# SFP.net
KiCad netlist of a schematic drawn in Altium Designer
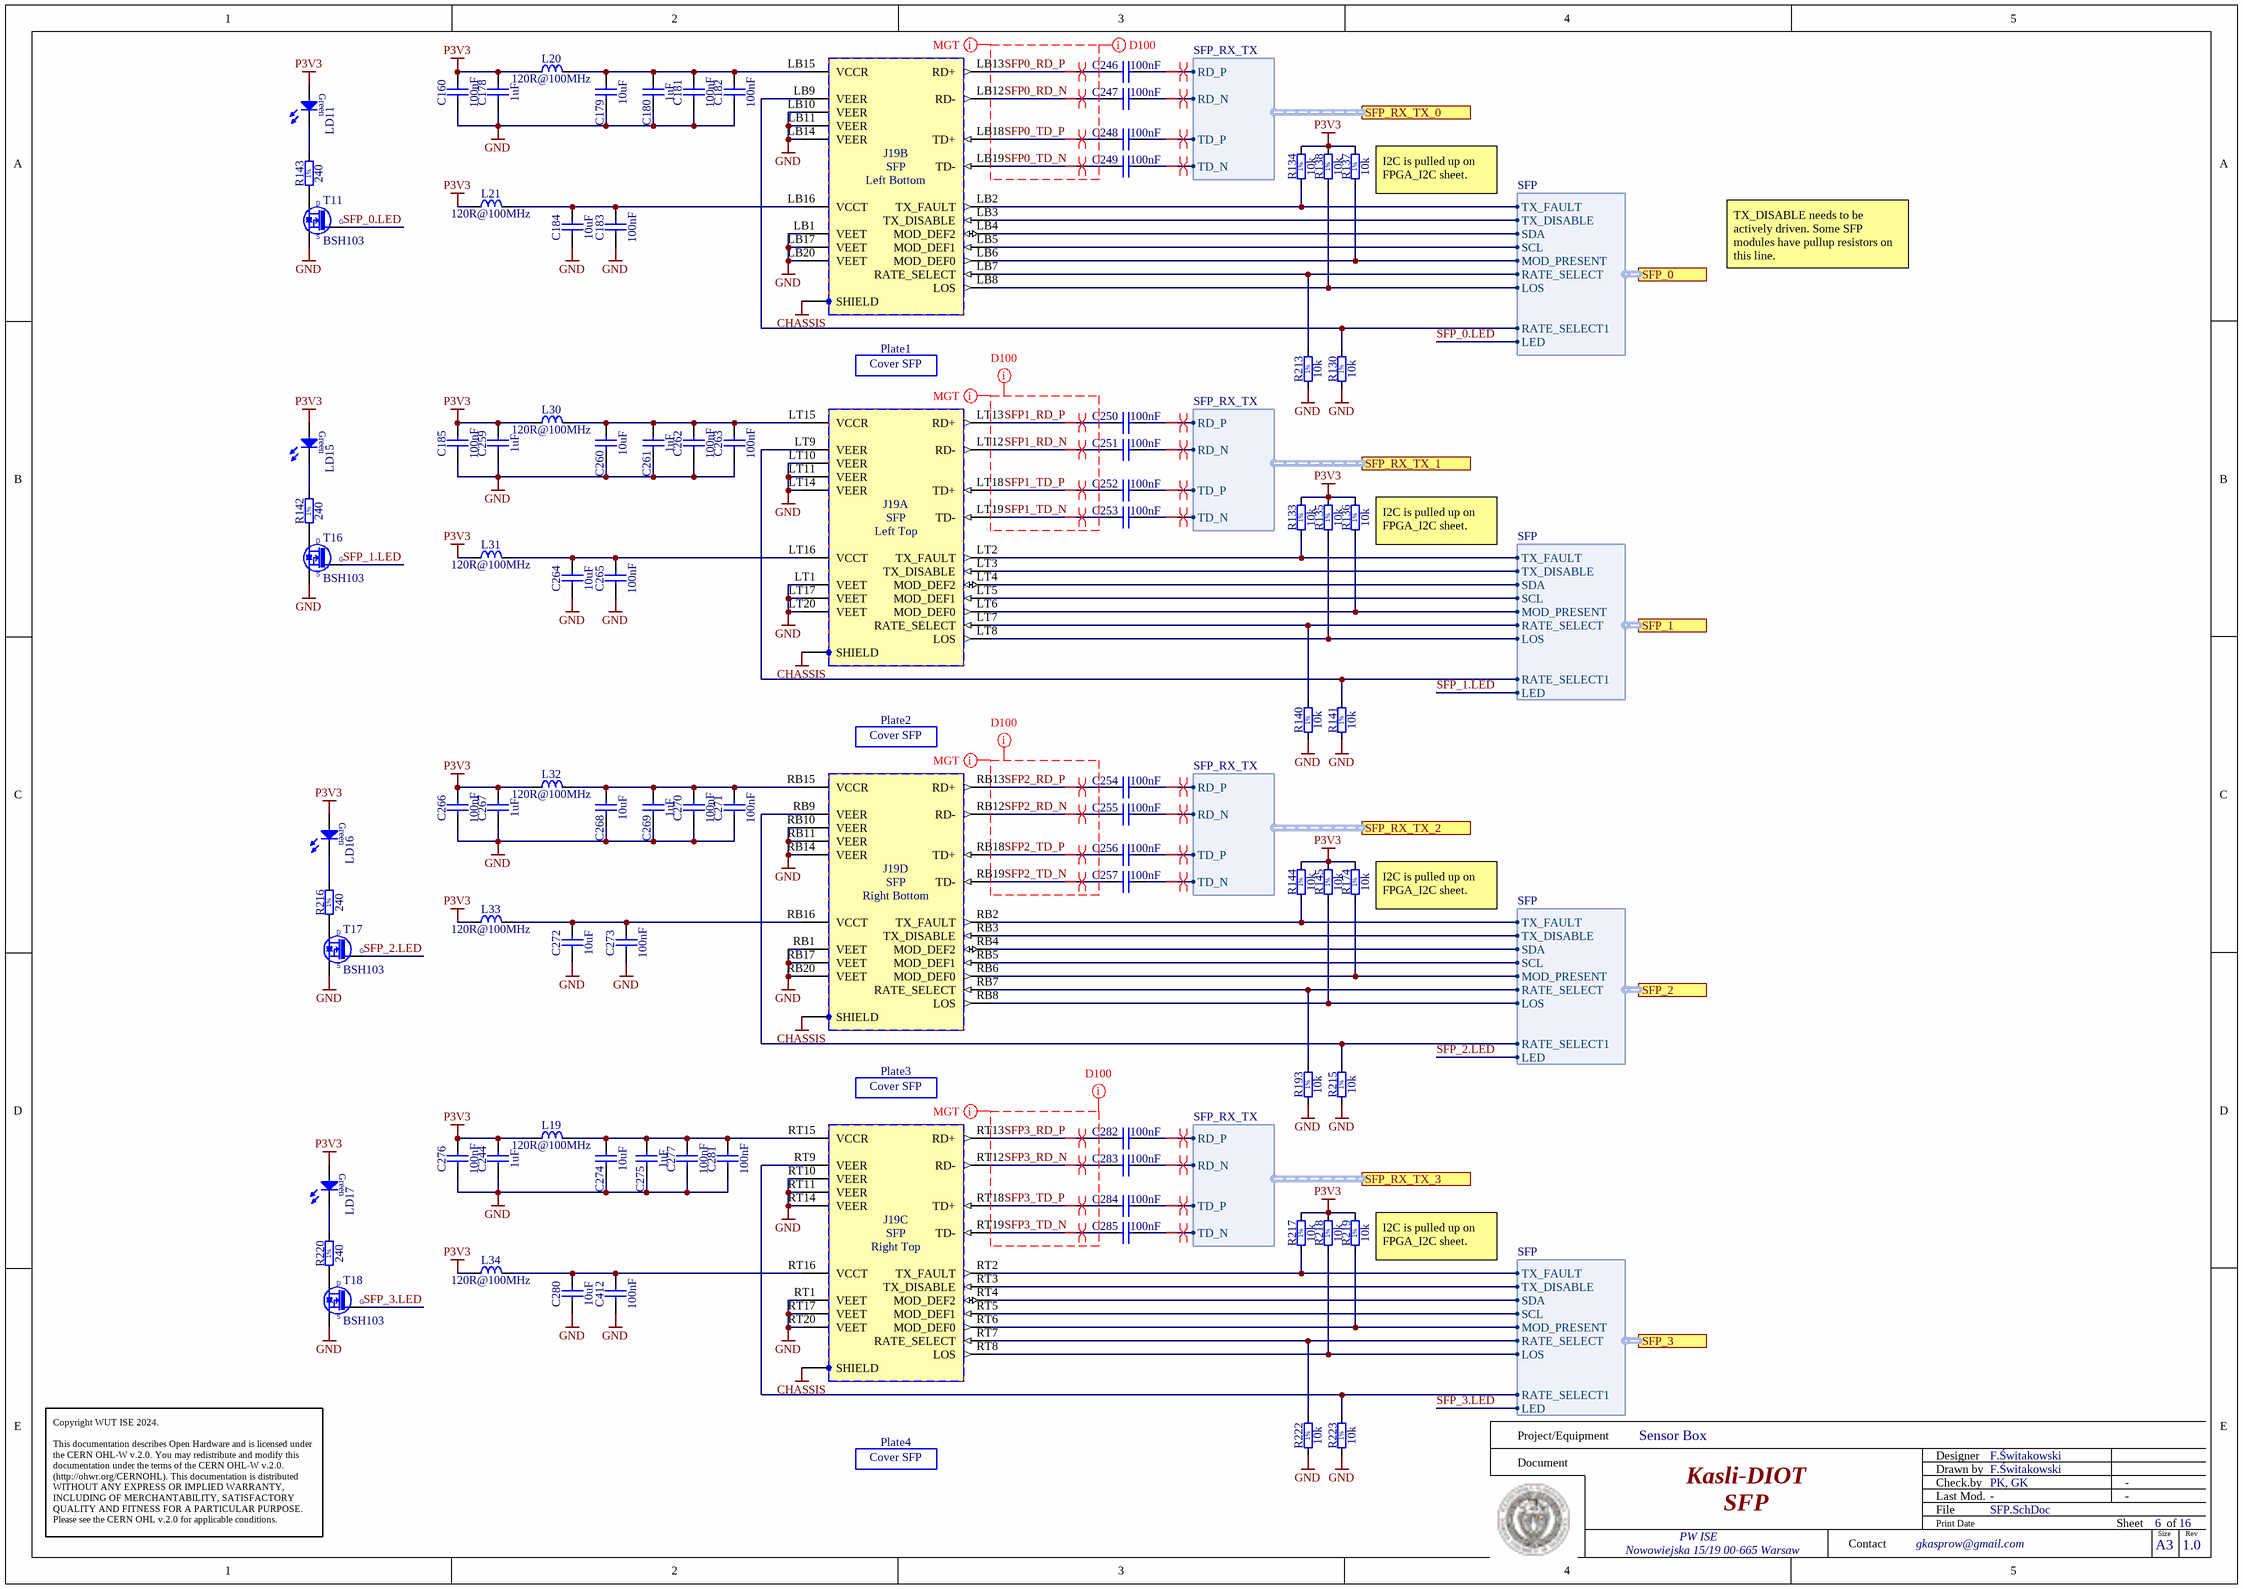
[diagram p0: SFP.SchDoc]

(export (version "E")
  (design (tool "Eeschema 10.0.6"))
  (components
    (comp (ref "C160")
      (value "100nF")
      (footprint "CAPC1005X55N")
      (description "Non-polarised capacitor")
      (fields (field (name "PART NUMBER") "CC0402_100NF_16V_10%_X7R") (field (name "VOLTAGE") "16V"))
      (libsource (lib "Capacitors") (part "Capacitor - non polarized"))
    )
    (comp (ref "C178")
      (value "1uF")
      (footprint "CAPC1005X55N")
      (description "Non-polarised capacitor")
      (fields (field (name "PART NUMBER") "CC0402_1UF_16V_10%_X5R") (field (name "VOLTAGE") "16V"))
      (libsource (lib "Capacitors") (part "Capacitor - non polarized"))
    )
    (comp (ref "C179")
      (value "10uF")
      (footprint "CAPC2012X95N")
      (description "Non-polarised capacitor")
      (fields (field (name "PART NUMBER") "CC0805_10UF_25V_10%_X5R") (field (name "VOLTAGE") "25V"))
      (libsource (lib "Capacitors") (part "Capacitor - non polarized"))
    )
    (comp (ref "C180")
      (value "1uF")
      (footprint "CAPC1005X55N")
      (description "Non-polarised capacitor")
      (fields (field (name "PART NUMBER") "CC0402_1UF_16V_10%_X5R") (field (name "VOLTAGE") "16V"))
      (libsource (lib "Capacitors") (part "Capacitor - non polarized"))
    )
    (comp (ref "C181")
      (value "100nF")
      (footprint "CAPC1005X55N")
      (description "Non-polarised capacitor")
      (fields (field (name "PART NUMBER") "CC0402_100NF_16V_10%_X7R") (field (name "VOLTAGE") "16V"))
      (libsource (lib "Capacitors") (part "Capacitor - non polarized"))
    )
    (comp (ref "C182")
      (value "100nF")
      (footprint "CAPC1005X55N")
      (description "Non-polarised capacitor")
      (fields (field (name "PART NUMBER") "CC0402_100NF_16V_10%_X7R") (field (name "VOLTAGE") "16V"))
      (libsource (lib "Capacitors") (part "Capacitor - non polarized"))
    )
    (comp (ref "C183")
      (value "100nF")
      (footprint "CAPC1005X55N")
      (description "Non-polarised capacitor")
      (fields (field (name "PART NUMBER") "CC0402_100NF_16V_10%_X7R") (field (name "VOLTAGE") "16V"))
      (libsource (lib "Capacitors") (part "Capacitor - non polarized"))
    )
    (comp (ref "C184")
      (value "10uF")
      (footprint "CAPC2012X95N")
      (description "Non-polarised capacitor")
      (fields (field (name "PART NUMBER") "CC0805_10UF_25V_10%_X5R") (field (name "VOLTAGE") "25V"))
      (libsource (lib "Capacitors") (part "Capacitor - non polarized"))
    )
    (comp (ref "C185")
      (value "100nF")
      (footprint "CAPC1005X55N")
      (description "Non-polarised capacitor")
      (fields (field (name "PART NUMBER") "CC0402_100NF_16V_10%_X7R") (field (name "VOLTAGE") "16V"))
      (libsource (lib "Capacitors") (part "Capacitor - non polarized"))
    )
    (comp (ref "C244")
      (value "1uF")
      (footprint "CAPC1005X55N")
      (description "Non-polarised capacitor")
      (fields (field (name "PART NUMBER") "CC0402_1UF_16V_10%_X5R") (field (name "VOLTAGE") "16V"))
      (libsource (lib "Capacitors") (part "Capacitor - non polarized"))
    )
    (comp (ref "C246")
      (value "100nF")
      (footprint "CAPC0603X33N")
      (description "Non-polarised capacitor")
      (fields (field (name "PART NUMBER") "CC0201_100NF_6.3V_10%_X5R") (field (name "VOLTAGE") "6.3V"))
      (libsource (lib "Capacitors") (part "Capacitor - non polarized"))
    )
    (comp (ref "C247")
      (value "100nF")
      (footprint "CAPC0603X33N")
      (description "Non-polarised capacitor")
      (fields (field (name "PART NUMBER") "CC0201_100NF_6.3V_10%_X5R") (field (name "VOLTAGE") "6.3V"))
      (libsource (lib "Capacitors") (part "Capacitor - non polarized"))
    )
    (comp (ref "C248")
      (value "100nF")
      (footprint "CAPC0603X33N")
      (description "Non-polarised capacitor")
      (fields (field (name "PART NUMBER") "CC0201_100NF_6.3V_10%_X5R") (field (name "VOLTAGE") "6.3V"))
      (libsource (lib "Capacitors") (part "Capacitor - non polarized"))
    )
    (comp (ref "C249")
      (value "100nF")
      (footprint "CAPC0603X33N")
      (description "Non-polarised capacitor")
      (fields (field (name "PART NUMBER") "CC0201_100NF_6.3V_10%_X5R") (field (name "VOLTAGE") "6.3V"))
      (libsource (lib "Capacitors") (part "Capacitor - non polarized"))
    )
    (comp (ref "C250")
      (value "100nF")
      (footprint "CAPC0603X33N")
      (description "Non-polarised capacitor")
      (fields (field (name "PART NUMBER") "CC0201_100NF_6.3V_10%_X5R") (field (name "VOLTAGE") "6.3V"))
      (libsource (lib "Capacitors") (part "Capacitor - non polarized"))
    )
    (comp (ref "C251")
      (value "100nF")
      (footprint "CAPC0603X33N")
      (description "Non-polarised capacitor")
      (fields (field (name "PART NUMBER") "CC0201_100NF_6.3V_10%_X5R") (field (name "VOLTAGE") "6.3V"))
      (libsource (lib "Capacitors") (part "Capacitor - non polarized"))
    )
    (comp (ref "C252")
      (value "100nF")
      (footprint "CAPC0603X33N")
      (description "Non-polarised capacitor")
      (fields (field (name "PART NUMBER") "CC0201_100NF_6.3V_10%_X5R") (field (name "VOLTAGE") "6.3V"))
      (libsource (lib "Capacitors") (part "Capacitor - non polarized"))
    )
    (comp (ref "C253")
      (value "100nF")
      (footprint "CAPC0603X33N")
      (description "Non-polarised capacitor")
      (fields (field (name "PART NUMBER") "CC0201_100NF_6.3V_10%_X5R") (field (name "VOLTAGE") "6.3V"))
      (libsource (lib "Capacitors") (part "Capacitor - non polarized"))
    )
    (comp (ref "C254")
      (value "100nF")
      (footprint "CAPC0603X33N")
      (description "Non-polarised capacitor")
      (fields (field (name "PART NUMBER") "CC0201_100NF_6.3V_10%_X5R") (field (name "VOLTAGE") "6.3V"))
      (libsource (lib "Capacitors") (part "Capacitor - non polarized"))
    )
    (comp (ref "C255")
      (value "100nF")
      (footprint "CAPC0603X33N")
      (description "Non-polarised capacitor")
      (fields (field (name "PART NUMBER") "CC0201_100NF_6.3V_10%_X5R") (field (name "VOLTAGE") "6.3V"))
      (libsource (lib "Capacitors") (part "Capacitor - non polarized"))
    )
    (comp (ref "C256")
      (value "100nF")
      (footprint "CAPC0603X33N")
      (description "Non-polarised capacitor")
      (fields (field (name "PART NUMBER") "CC0201_100NF_6.3V_10%_X5R") (field (name "VOLTAGE") "6.3V"))
      (libsource (lib "Capacitors") (part "Capacitor - non polarized"))
    )
    (comp (ref "C257")
      (value "100nF")
      (footprint "CAPC0603X33N")
      (description "Non-polarised capacitor")
      (fields (field (name "PART NUMBER") "CC0201_100NF_6.3V_10%_X5R") (field (name "VOLTAGE") "6.3V"))
      (libsource (lib "Capacitors") (part "Capacitor - non polarized"))
    )
    (comp (ref "C259")
      (value "1uF")
      (footprint "CAPC1005X55N")
      (description "Non-polarised capacitor")
      (fields (field (name "PART NUMBER") "CC0402_1UF_16V_10%_X5R") (field (name "VOLTAGE") "16V"))
      (libsource (lib "Capacitors") (part "Capacitor - non polarized"))
    )
    (comp (ref "C260")
      (value "10uF")
      (footprint "CAPC2012X95N")
      (description "Non-polarised capacitor")
      (fields (field (name "PART NUMBER") "CC0805_10UF_25V_10%_X5R") (field (name "VOLTAGE") "25V"))
      (libsource (lib "Capacitors") (part "Capacitor - non polarized"))
    )
    (comp (ref "C261")
      (value "1uF")
      (footprint "CAPC1005X55N")
      (description "Non-polarised capacitor")
      (fields (field (name "PART NUMBER") "CC0402_1UF_16V_10%_X5R") (field (name "VOLTAGE") "16V"))
      (libsource (lib "Capacitors") (part "Capacitor - non polarized"))
    )
    (comp (ref "C262")
      (value "100nF")
      (footprint "CAPC1005X55N")
      (description "Non-polarised capacitor")
      (fields (field (name "PART NUMBER") "CC0402_100NF_16V_10%_X7R") (field (name "VOLTAGE") "16V"))
      (libsource (lib "Capacitors") (part "Capacitor - non polarized"))
    )
    (comp (ref "C263")
      (value "100nF")
      (footprint "CAPC1005X55N")
      (description "Non-polarised capacitor")
      (fields (field (name "PART NUMBER") "CC0402_100NF_16V_10%_X7R") (field (name "VOLTAGE") "16V"))
      (libsource (lib "Capacitors") (part "Capacitor - non polarized"))
    )
    (comp (ref "C264")
      (value "10uF")
      (footprint "CAPC2012X95N")
      (description "Non-polarised capacitor")
      (fields (field (name "PART NUMBER") "CC0805_10UF_25V_10%_X5R") (field (name "VOLTAGE") "25V"))
      (libsource (lib "Capacitors") (part "Capacitor - non polarized"))
    )
    (comp (ref "C265")
      (value "100nF")
      (footprint "CAPC1005X55N")
      (description "Non-polarised capacitor")
      (fields (field (name "PART NUMBER") "CC0402_100NF_16V_10%_X7R") (field (name "VOLTAGE") "16V"))
      (libsource (lib "Capacitors") (part "Capacitor - non polarized"))
    )
    (comp (ref "C266")
      (value "100nF")
      (footprint "CAPC1005X55N")
      (description "Non-polarised capacitor")
      (fields (field (name "PART NUMBER") "CC0402_100NF_16V_10%_X7R") (field (name "VOLTAGE") "16V"))
      (libsource (lib "Capacitors") (part "Capacitor - non polarized"))
    )
    (comp (ref "C267")
      (value "1uF")
      (footprint "CAPC1005X55N")
      (description "Non-polarised capacitor")
      (fields (field (name "PART NUMBER") "CC0402_1UF_16V_10%_X5R") (field (name "VOLTAGE") "16V"))
      (libsource (lib "Capacitors") (part "Capacitor - non polarized"))
    )
    (comp (ref "C268")
      (value "10uF")
      (footprint "CAPC2012X95N")
      (description "Non-polarised capacitor")
      (fields (field (name "PART NUMBER") "CC0805_10UF_25V_10%_X5R") (field (name "VOLTAGE") "25V"))
      (libsource (lib "Capacitors") (part "Capacitor - non polarized"))
    )
    (comp (ref "C269")
      (value "1uF")
      (footprint "CAPC1005X55N")
      (description "Non-polarised capacitor")
      (fields (field (name "PART NUMBER") "CC0402_1UF_16V_10%_X5R") (field (name "VOLTAGE") "16V"))
      (libsource (lib "Capacitors") (part "Capacitor - non polarized"))
    )
    (comp (ref "C270")
      (value "100nF")
      (footprint "CAPC1005X55N")
      (description "Non-polarised capacitor")
      (fields (field (name "PART NUMBER") "CC0402_100NF_16V_10%_X7R") (field (name "VOLTAGE") "16V"))
      (libsource (lib "Capacitors") (part "Capacitor - non polarized"))
    )
    (comp (ref "C271")
      (value "100nF")
      (footprint "CAPC1005X55N")
      (description "Non-polarised capacitor")
      (fields (field (name "PART NUMBER") "CC0402_100NF_16V_10%_X7R") (field (name "VOLTAGE") "16V"))
      (libsource (lib "Capacitors") (part "Capacitor - non polarized"))
    )
    (comp (ref "C272")
      (value "10uF")
      (footprint "CAPC2012X95N")
      (description "Non-polarised capacitor")
      (fields (field (name "PART NUMBER") "CC0805_10UF_25V_10%_X5R") (field (name "VOLTAGE") "25V"))
      (libsource (lib "Capacitors") (part "Capacitor - non polarized"))
    )
    (comp (ref "C273")
      (value "100nF")
      (footprint "CAPC1005X55N")
      (description "Non-polarised capacitor")
      (fields (field (name "PART NUMBER") "CC0402_100NF_16V_10%_X7R") (field (name "VOLTAGE") "16V"))
      (libsource (lib "Capacitors") (part "Capacitor - non polarized"))
    )
    (comp (ref "C274")
      (value "10uF")
      (footprint "CAPC2012X95N")
      (description "Non-polarised capacitor")
      (fields (field (name "PART NUMBER") "CC0805_10UF_25V_10%_X5R") (field (name "VOLTAGE") "25V"))
      (libsource (lib "Capacitors") (part "Capacitor - non polarized"))
    )
    (comp (ref "C275")
      (value "1uF")
      (footprint "CAPC1005X55N")
      (description "Non-polarised capacitor")
      (fields (field (name "PART NUMBER") "CC0402_1UF_16V_10%_X5R") (field (name "VOLTAGE") "16V"))
      (libsource (lib "Capacitors") (part "Capacitor - non polarized"))
    )
    (comp (ref "C276")
      (value "100nF")
      (footprint "CAPC1005X55N")
      (description "Non-polarised capacitor")
      (fields (field (name "PART NUMBER") "CC0402_100NF_16V_10%_X7R") (field (name "VOLTAGE") "16V"))
      (libsource (lib "Capacitors") (part "Capacitor - non polarized"))
    )
    (comp (ref "C277")
      (value "100nF")
      (footprint "CAPC1005X55N")
      (description "Non-polarised capacitor")
      (fields (field (name "PART NUMBER") "CC0402_100NF_16V_10%_X7R") (field (name "VOLTAGE") "16V"))
      (libsource (lib "Capacitors") (part "Capacitor - non polarized"))
    )
    (comp (ref "C280")
      (value "10uF")
      (footprint "CAPC2012X95N")
      (description "Non-polarised capacitor")
      (fields (field (name "PART NUMBER") "CC0805_10UF_25V_10%_X5R") (field (name "VOLTAGE") "25V"))
      (libsource (lib "Capacitors") (part "Capacitor - non polarized"))
    )
    (comp (ref "C281")
      (value "100nF")
      (footprint "CAPC1005X55N")
      (description "Non-polarised capacitor")
      (fields (field (name "PART NUMBER") "CC0402_100NF_16V_10%_X7R") (field (name "VOLTAGE") "16V"))
      (libsource (lib "Capacitors") (part "Capacitor - non polarized"))
    )
    (comp (ref "C282")
      (value "100nF")
      (footprint "CAPC0603X33N")
      (description "Non-polarised capacitor")
      (fields (field (name "PART NUMBER") "CC0201_100NF_6.3V_10%_X5R") (field (name "VOLTAGE") "6.3V"))
      (libsource (lib "Capacitors") (part "Capacitor - non polarized"))
    )
    (comp (ref "C283")
      (value "100nF")
      (footprint "CAPC0603X33N")
      (description "Non-polarised capacitor")
      (fields (field (name "PART NUMBER") "CC0201_100NF_6.3V_10%_X5R") (field (name "VOLTAGE") "6.3V"))
      (libsource (lib "Capacitors") (part "Capacitor - non polarized"))
    )
    (comp (ref "C284")
      (value "100nF")
      (footprint "CAPC0603X33N")
      (description "Non-polarised capacitor")
      (fields (field (name "PART NUMBER") "CC0201_100NF_6.3V_10%_X5R") (field (name "VOLTAGE") "6.3V"))
      (libsource (lib "Capacitors") (part "Capacitor - non polarized"))
    )
    (comp (ref "C285")
      (value "100nF")
      (footprint "CAPC0603X33N")
      (description "Non-polarised capacitor")
      (fields (field (name "PART NUMBER") "CC0201_100NF_6.3V_10%_X5R") (field (name "VOLTAGE") "6.3V"))
      (libsource (lib "Capacitors") (part "Capacitor - non polarized"))
    )
    (comp (ref "C412")
      (value "100nF")
      (footprint "CAPC1005X55N")
      (description "Non-polarised capacitor")
      (fields (field (name "PART NUMBER") "CC0402_100NF_16V_10%_X7R") (field (name "VOLTAGE") "16V"))
      (libsource (lib "Capacitors") (part "Capacitor - non polarized"))
    )
    (comp (ref "J19")
      (value "SFP")
      (footprint "AMPHENOL_UE78B212700321")
      (description "20 Position SFP  Connector (Small Form-factor Pluggable)")
      (fields (field (name "PART NUMBER") "AMPHENOL_UE78B212700321") (field (name "MANUFACTURER") "AMPHENOL"))
      (libsource (lib "Connectors") (part "SFP 2x2 +Cage"))
    )
    (comp (ref "L19")
      (value "120R@100MHz")
      (footprint "INDC1608X65N")
      (description "Inductor")
      (fields (field (name "PART NUMBER") "IND0603_MURATA_BLM18SG121TN1D") (field (name "POWER") "3A"))
      (libsource (lib "Inductors & Transformers") (part "Inductor"))
    )
    (comp (ref "L20")
      (value "120R@100MHz")
      (footprint "INDC1608X65N")
      (description "Inductor")
      (fields (field (name "PART NUMBER") "IND0603_MURATA_BLM18SG121TN1D") (field (name "POWER") "3A"))
      (libsource (lib "Inductors & Transformers") (part "Inductor"))
    )
    (comp (ref "L21")
      (value "120R@100MHz")
      (footprint "INDC1608X65N")
      (description "Inductor")
      (fields (field (name "PART NUMBER") "IND0603_MURATA_BLM18SG121TN1D") (field (name "POWER") "3A"))
      (libsource (lib "Inductors & Transformers") (part "Inductor"))
    )
    (comp (ref "L30")
      (value "120R@100MHz")
      (footprint "INDC1608X65N")
      (description "Inductor")
      (fields (field (name "PART NUMBER") "IND0603_MURATA_BLM18SG121TN1D") (field (name "POWER") "3A"))
      (libsource (lib "Inductors & Transformers") (part "Inductor"))
    )
    (comp (ref "L31")
      (value "120R@100MHz")
      (footprint "INDC1608X65N")
      (description "Inductor")
      (fields (field (name "PART NUMBER") "IND0603_MURATA_BLM18SG121TN1D") (field (name "POWER") "3A"))
      (libsource (lib "Inductors & Transformers") (part "Inductor"))
    )
    (comp (ref "L32")
      (value "120R@100MHz")
      (footprint "INDC1608X65N")
      (description "Inductor")
      (fields (field (name "PART NUMBER") "IND0603_MURATA_BLM18SG121TN1D") (field (name "POWER") "3A"))
      (libsource (lib "Inductors & Transformers") (part "Inductor"))
    )
    (comp (ref "L33")
      (value "120R@100MHz")
      (footprint "INDC1608X65N")
      (description "Inductor")
      (fields (field (name "PART NUMBER") "IND0603_MURATA_BLM18SG121TN1D") (field (name "POWER") "3A"))
      (libsource (lib "Inductors & Transformers") (part "Inductor"))
    )
    (comp (ref "L34")
      (value "120R@100MHz")
      (footprint "INDC1608X65N")
      (description "Inductor")
      (fields (field (name "PART NUMBER") "IND0603_MURATA_BLM18SG121TN1D") (field (name "POWER") "3A"))
      (libsource (lib "Inductors & Transformers") (part "Inductor"))
    )
    (comp (ref "LD11")
      (value "Green")
      (footprint "LED_AVAGO_HSME-C120")
      (description "LED Green 1C 2A")
      (fields
        (field (name "PART NUMBER") "LED_AVAGO_HSME-C120")
        (field (name "MANUFACTURER") "AVAGO TECHNOLOGIES")
      )
      (libsource (lib "ICs And Semiconductors") (part "LED Green 1C 2A"))
    )
    (comp (ref "LD15")
      (value "Green")
      (footprint "LED_AVAGO_HSME-C120")
      (description "LED Green 1C 2A")
      (fields
        (field (name "PART NUMBER") "LED_AVAGO_HSME-C120")
        (field (name "MANUFACTURER") "AVAGO TECHNOLOGIES")
      )
      (libsource (lib "ICs And Semiconductors") (part "LED Green 1C 2A"))
    )
    (comp (ref "LD16")
      (value "Green")
      (footprint "LED_AVAGO_HSME-C120")
      (description "LED Green 1C 2A")
      (fields
        (field (name "PART NUMBER") "LED_AVAGO_HSME-C120")
        (field (name "MANUFACTURER") "AVAGO TECHNOLOGIES")
      )
      (libsource (lib "ICs And Semiconductors") (part "LED Green 1C 2A"))
    )
    (comp (ref "LD17")
      (value "Green")
      (footprint "LED_AVAGO_HSME-C120")
      (description "LED Green 1C 2A")
      (fields
        (field (name "PART NUMBER") "LED_AVAGO_HSME-C120")
        (field (name "MANUFACTURER") "AVAGO TECHNOLOGIES")
      )
      (libsource (lib "ICs And Semiconductors") (part "LED Green 1C 2A"))
    )
    (comp (ref "Plate1")
      (value "Cover SFP")
      (footprint "AMPHENOL_U77A11108000P")
      (description "Plastic Dust Cover SFP Cage")
      (fields (field (name "PART NUMBER") "AMPHENOL_U77A11108000P") (field (name "MANUFACTURER") "AMPHENOL"))
      (libsource (lib "Eletro-mechanical") (part "SFP Cover No Pin"))
    )
    (comp (ref "Plate2")
      (value "Cover SFP")
      (footprint "AMPHENOL_U77A11108000P")
      (description "Plastic Dust Cover SFP Cage")
      (fields
        (field (name "MANUFACTURER") "AMPHENOL")
        (field (name "MANUFACTURER PART NUMBER") "U77A11108000P")
      )
      (libsource (lib "Eletro-mechanical") (part "SFP Cover No Pin"))
    )
    (comp (ref "Plate3")
      (value "Cover SFP")
      (footprint "AMPHENOL_U77A11108000P")
      (description "Plastic Dust Cover SFP Cage")
      (fields
        (field (name "MANUFACTURER") "AMPHENOL")
        (field (name "MANUFACTURER PART NUMBER") "U77A11108000P")
      )
      (libsource (lib "Eletro-mechanical") (part "SFP Cover No Pin"))
    )
    (comp (ref "Plate4")
      (value "Cover SFP")
      (footprint "AMPHENOL_U77A11108000P")
      (description "Plastic Dust Cover SFP Cage")
      (fields
        (field (name "MANUFACTURER") "AMPHENOL")
        (field (name "MANUFACTURER PART NUMBER") "U77A11108000P")
      )
      (libsource (lib "Eletro-mechanical") (part "SFP Cover No Pin"))
    )
    (comp (ref "R130")
      (value "10k")
      (footprint "RESC1005X40N")
      (description "Resistor - 1%")
      (fields (field (name "PART NUMBER") "R0402_10K_1%_0.0625W_100PPM") (field (name "POWER") "0.0625W"))
      (libsource (lib "Resistors") (part "Resistor - 1%"))
    )
    (comp (ref "R133")
      (value "10k")
      (footprint "RESC1005X40N")
      (description "Resistor - 1%")
      (fields (field (name "PART NUMBER") "R0402_10K_1%_0.0625W_100PPM") (field (name "POWER") "0.0625W"))
      (libsource (lib "Resistors") (part "Resistor - 1%"))
    )
    (comp (ref "R134")
      (value "10k")
      (footprint "RESC1005X40N")
      (description "Resistor - 1%")
      (fields (field (name "PART NUMBER") "R0402_10K_1%_0.0625W_100PPM") (field (name "POWER") "0.0625W"))
      (libsource (lib "Resistors") (part "Resistor - 1%"))
    )
    (comp (ref "R135")
      (value "10k")
      (footprint "RESC1005X40N")
      (description "Resistor - 1%")
      (fields (field (name "PART NUMBER") "R0402_10K_1%_0.0625W_100PPM") (field (name "POWER") "0.0625W"))
      (libsource (lib "Resistors") (part "Resistor - 1%"))
    )
    (comp (ref "R136")
      (value "10k")
      (footprint "RESC1005X40N")
      (description "Resistor - 1%")
      (fields (field (name "PART NUMBER") "R0402_10K_1%_0.0625W_100PPM") (field (name "POWER") "0.0625W"))
      (libsource (lib "Resistors") (part "Resistor - 1%"))
    )
    (comp (ref "R137")
      (value "10k")
      (footprint "RESC1005X40N")
      (description "Resistor - 1%")
      (fields (field (name "PART NUMBER") "R0402_10K_1%_0.0625W_100PPM") (field (name "POWER") "0.0625W"))
      (libsource (lib "Resistors") (part "Resistor - 1%"))
    )
    (comp (ref "R138")
      (value "10k")
      (footprint "RESC1005X40N")
      (description "Resistor - 1%")
      (fields (field (name "PART NUMBER") "R0402_10K_1%_0.0625W_100PPM") (field (name "POWER") "0.0625W"))
      (libsource (lib "Resistors") (part "Resistor - 1%"))
    )
    (comp (ref "R140")
      (value "10k")
      (footprint "RESC1005X40N")
      (description "Resistor - 1%")
      (fields (field (name "PART NUMBER") "R0402_10K_1%_0.0625W_100PPM") (field (name "POWER") "0.0625W"))
      (libsource (lib "Resistors") (part "Resistor - 1%"))
    )
    (comp (ref "R141")
      (value "10k")
      (footprint "RESC1005X40N")
      (description "Resistor - 1%")
      (fields (field (name "PART NUMBER") "R0402_10K_1%_0.0625W_100PPM") (field (name "POWER") "0.0625W"))
      (libsource (lib "Resistors") (part "Resistor - 1%"))
    )
    (comp (ref "R142")
      (value "240")
      (footprint "RESC1005X40N")
      (description "Resistor - 1%")
      (fields (field (name "PART NUMBER") "R0402_240R_1%_0.0625W_100PPM") (field (name "POWER") "0.0625W"))
      (libsource (lib "Resistors") (part "Resistor - 1%"))
    )
    (comp (ref "R143")
      (value "240")
      (footprint "RESC1005X40N")
      (description "Resistor - 1%")
      (fields (field (name "PART NUMBER") "R0402_240R_1%_0.0625W_100PPM") (field (name "POWER") "0.0625W"))
      (libsource (lib "Resistors") (part "Resistor - 1%"))
    )
    (comp (ref "R144")
      (value "10k")
      (footprint "RESC1005X40N")
      (description "Resistor - 1%")
      (fields (field (name "PART NUMBER") "R0402_10K_1%_0.0625W_100PPM") (field (name "POWER") "0.0625W"))
      (libsource (lib "Resistors") (part "Resistor - 1%"))
    )
    (comp (ref "R145")
      (value "10k")
      (footprint "RESC1005X40N")
      (description "Resistor - 1%")
      (fields (field (name "PART NUMBER") "R0402_10K_1%_0.0625W_100PPM") (field (name "POWER") "0.0625W"))
      (libsource (lib "Resistors") (part "Resistor - 1%"))
    )
    (comp (ref "R174")
      (value "10k")
      (footprint "RESC1005X40N")
      (description "Resistor - 1%")
      (fields (field (name "PART NUMBER") "R0402_10K_1%_0.0625W_100PPM") (field (name "POWER") "0.0625W"))
      (libsource (lib "Resistors") (part "Resistor - 1%"))
    )
    (comp (ref "R193")
      (value "10k")
      (footprint "RESC1005X40N")
      (description "Resistor - 1%")
      (fields (field (name "PART NUMBER") "R0402_10K_1%_0.0625W_100PPM") (field (name "POWER") "0.0625W"))
      (libsource (lib "Resistors") (part "Resistor - 1%"))
    )
    (comp (ref "R213")
      (value "10k")
      (footprint "RESC1005X40N")
      (description "Resistor - 1%")
      (fields (field (name "PART NUMBER") "R0402_10K_1%_0.0625W_100PPM") (field (name "POWER") "0.0625W"))
      (libsource (lib "Resistors") (part "Resistor - 1%"))
    )
    (comp (ref "R215")
      (value "10k")
      (footprint "RESC1005X40N")
      (description "Resistor - 1%")
      (fields (field (name "PART NUMBER") "R0402_10K_1%_0.0625W_100PPM") (field (name "POWER") "0.0625W"))
      (libsource (lib "Resistors") (part "Resistor - 1%"))
    )
    (comp (ref "R216")
      (value "240")
      (footprint "RESC1005X40N")
      (description "Resistor - 1%")
      (fields (field (name "PART NUMBER") "R0402_240R_1%_0.0625W_100PPM") (field (name "POWER") "0.0625W"))
      (libsource (lib "Resistors") (part "Resistor - 1%"))
    )
    (comp (ref "R217")
      (value "10k")
      (footprint "RESC1005X40N")
      (description "Resistor - 1%")
      (fields (field (name "PART NUMBER") "R0402_10K_1%_0.0625W_100PPM") (field (name "POWER") "0.0625W"))
      (libsource (lib "Resistors") (part "Resistor - 1%"))
    )
    (comp (ref "R218")
      (value "10k")
      (footprint "RESC1005X40N")
      (description "Resistor - 1%")
      (fields (field (name "PART NUMBER") "R0402_10K_1%_0.0625W_100PPM") (field (name "POWER") "0.0625W"))
      (libsource (lib "Resistors") (part "Resistor - 1%"))
    )
    (comp (ref "R219")
      (value "10k")
      (footprint "RESC1005X40N")
      (description "Resistor - 1%")
      (fields (field (name "PART NUMBER") "R0402_10K_1%_0.0625W_100PPM") (field (name "POWER") "0.0625W"))
      (libsource (lib "Resistors") (part "Resistor - 1%"))
    )
    (comp (ref "R220")
      (value "240")
      (footprint "RESC1005X40N")
      (description "Resistor - 1%")
      (fields (field (name "PART NUMBER") "R0402_240R_1%_0.0625W_100PPM") (field (name "POWER") "0.0625W"))
      (libsource (lib "Resistors") (part "Resistor - 1%"))
    )
    (comp (ref "R222")
      (value "10k")
      (footprint "RESC1005X40N")
      (description "Resistor - 1%")
      (fields (field (name "PART NUMBER") "R0402_10K_1%_0.0625W_100PPM") (field (name "POWER") "0.0625W"))
      (libsource (lib "Resistors") (part "Resistor - 1%"))
    )
    (comp (ref "R223")
      (value "10k")
      (footprint "RESC1005X40N")
      (description "Resistor - 1%")
      (fields (field (name "PART NUMBER") "R0402_10K_1%_0.0625W_100PPM") (field (name "POWER") "0.0625W"))
      (libsource (lib "Resistors") (part "Resistor - 1%"))
    )
    (comp (ref "T11")
      (value "BSH103")
      (footprint "SOT95P230X110-3N")
      (description "N-CHANNEL MOSFET WITH DIODE")
      (fields (field (name "MANUFACTURER") "NEXPERIA"))
      (libsource (lib "ICs And Semiconductors") (part "N-MOSFET-D 1G 2S 3D"))
    )
    (comp (ref "T16")
      (value "BSH103")
      (footprint "SOT95P230X110-3N")
      (description "N-CHANNEL MOSFET WITH DIODE")
      (fields (field (name "MANUFACTURER") "NEXPERIA"))
      (libsource (lib "ICs And Semiconductors") (part "N-MOSFET-D 1G 2S 3D"))
    )
    (comp (ref "T17")
      (value "BSH103")
      (footprint "SOT95P230X110-3N")
      (description "N-CHANNEL MOSFET WITH DIODE")
      (fields (field (name "MANUFACTURER") "NEXPERIA"))
      (libsource (lib "ICs And Semiconductors") (part "N-MOSFET-D 1G 2S 3D"))
    )
    (comp (ref "T18")
      (value "BSH103")
      (footprint "SOT95P230X110-3N")
      (description "N-CHANNEL MOSFET WITH DIODE")
      (fields (field (name "MANUFACTURER") "NEXPERIA"))
      (libsource (lib "ICs And Semiconductors") (part "N-MOSFET-D 1G 2S 3D"))
    )
  )
  (nets
    (net (code "3") (name "/SFP0_RD_N") (class "Default")
      (node (ref "C247") (pin "1") (pinfunction "1_1") (pintype "passive"))
      (node (ref "J19") (pin "LB12") (pinfunction "RD-_LB12") (pintype "output"))
    )
    (net (code "4") (name "/SFP0_RD_P") (class "Default")
      (node (ref "C246") (pin "1") (pinfunction "1_1") (pintype "passive"))
      (node (ref "J19") (pin "LB13") (pinfunction "RD+_LB13") (pintype "output"))
    )
    (net (code "5") (name "/SFP0_TD_N") (class "Default")
      (node (ref "C249") (pin "1") (pinfunction "1_1") (pintype "passive"))
      (node (ref "J19") (pin "LB19") (pinfunction "TD-_LB19") (pintype "input"))
    )
    (net (code "6") (name "/SFP0_TD_P") (class "Default")
      (node (ref "C248") (pin "1") (pinfunction "1_1") (pintype "passive"))
      (node (ref "J19") (pin "LB18") (pinfunction "TD+_LB18") (pintype "input"))
    )
    (net (code "7") (name "/SFP1_RD_N") (class "Default")
      (node (ref "C251") (pin "1") (pinfunction "1_1") (pintype "passive"))
      (node (ref "J19") (pin "LT12") (pinfunction "RD-_LT12") (pintype "output"))
    )
    (net (code "8") (name "/SFP1_RD_P") (class "Default")
      (node (ref "C250") (pin "1") (pinfunction "1_1") (pintype "passive"))
      (node (ref "J19") (pin "LT13") (pinfunction "RD+_LT13") (pintype "output"))
    )
    (net (code "9") (name "/SFP1_TD_N") (class "Default")
      (node (ref "C253") (pin "1") (pinfunction "1_1") (pintype "passive"))
      (node (ref "J19") (pin "LT19") (pinfunction "TD-_LT19") (pintype "input"))
    )
    (net (code "10") (name "/SFP1_TD_P") (class "Default")
      (node (ref "C252") (pin "1") (pinfunction "1_1") (pintype "passive"))
      (node (ref "J19") (pin "LT18") (pinfunction "TD+_LT18") (pintype "input"))
    )
    (net (code "11") (name "/SFP2_RD_N") (class "Default")
      (node (ref "C255") (pin "1") (pinfunction "1_1") (pintype "passive"))
      (node (ref "J19") (pin "RB12") (pinfunction "RD-_RB12") (pintype "output"))
    )
    (net (code "12") (name "/SFP2_RD_P") (class "Default")
      (node (ref "C254") (pin "1") (pinfunction "1_1") (pintype "passive"))
      (node (ref "J19") (pin "RB13") (pinfunction "RD+_RB13") (pintype "output"))
    )
    (net (code "13") (name "/SFP2_TD_N") (class "Default")
      (node (ref "C257") (pin "1") (pinfunction "1_1") (pintype "passive"))
      (node (ref "J19") (pin "RB19") (pinfunction "TD-_RB19") (pintype "input"))
    )
    (net (code "14") (name "/SFP2_TD_P") (class "Default")
      (node (ref "C256") (pin "1") (pinfunction "1_1") (pintype "passive"))
      (node (ref "J19") (pin "RB18") (pinfunction "TD+_RB18") (pintype "input"))
    )
    (net (code "15") (name "/SFP3_RD_N") (class "Default")
      (node (ref "C283") (pin "1") (pinfunction "1_1") (pintype "passive"))
      (node (ref "J19") (pin "RT12") (pinfunction "RD-_RT12") (pintype "output"))
    )
    (net (code "16") (name "/SFP3_RD_P") (class "Default")
      (node (ref "C282") (pin "1") (pinfunction "1_1") (pintype "passive"))
      (node (ref "J19") (pin "RT13") (pinfunction "RD+_RT13") (pintype "output"))
    )
    (net (code "17") (name "/SFP3_TD_N") (class "Default")
      (node (ref "C285") (pin "1") (pinfunction "1_1") (pintype "passive"))
      (node (ref "J19") (pin "RT19") (pinfunction "TD-_RT19") (pintype "input"))
    )
    (net (code "18") (name "/SFP3_TD_P") (class "Default")
      (node (ref "C284") (pin "1") (pinfunction "1_1") (pintype "passive"))
      (node (ref "J19") (pin "RT18") (pinfunction "TD+_RT18") (pintype "input"))
    )
    (net (code "19") (name "/SFP_0.LED") (class "Default")
      (node (ref "T11") (pin "1") (pinfunction "G_1") (pintype "passive"))
    )
    (net (code "20") (name "/SFP_1.LED") (class "Default")
      (node (ref "T16") (pin "1") (pinfunction "G_1") (pintype "passive"))
    )
    (net (code "21") (name "/SFP_2.LED") (class "Default")
      (node (ref "T17") (pin "1") (pinfunction "G_1") (pintype "passive"))
    )
    (net (code "22") (name "/SFP_3.LED") (class "Default")
      (node (ref "T18") (pin "1") (pinfunction "G_1") (pintype "passive"))
    )
    (net (code "25") (name "CHASSIS") (class "Default")
      (node (ref "J19") (pin "SHIELD") (pinfunction "SHIELD_SHIELD") (pintype "power_in"))
    )
    (net (code "26") (name "GND") (class "Default")
      (node (ref "C160") (pin "1") (pinfunction "1_1") (pintype "passive"))
      (node (ref "C178") (pin "1") (pinfunction "1_1") (pintype "passive"))
      (node (ref "C179") (pin "1") (pinfunction "1_1") (pintype "passive"))
      (node (ref "C180") (pin "1") (pinfunction "1_1") (pintype "passive"))
      (node (ref "C181") (pin "1") (pinfunction "1_1") (pintype "passive"))
      (node (ref "C182") (pin "1") (pinfunction "1_1") (pintype "passive"))
      (node (ref "C183") (pin "1") (pinfunction "1_1") (pintype "passive"))
      (node (ref "C184") (pin "1") (pinfunction "1_1") (pintype "passive"))
      (node (ref "C185") (pin "1") (pinfunction "1_1") (pintype "passive"))
      (node (ref "C244") (pin "1") (pinfunction "1_1") (pintype "passive"))
      (node (ref "C259") (pin "1") (pinfunction "1_1") (pintype "passive"))
      (node (ref "C260") (pin "1") (pinfunction "1_1") (pintype "passive"))
      (node (ref "C261") (pin "1") (pinfunction "1_1") (pintype "passive"))
      (node (ref "C262") (pin "1") (pinfunction "1_1") (pintype "passive"))
      (node (ref "C263") (pin "1") (pinfunction "1_1") (pintype "passive"))
      (node (ref "C264") (pin "1") (pinfunction "1_1") (pintype "passive"))
      (node (ref "C265") (pin "1") (pinfunction "1_1") (pintype "passive"))
      (node (ref "C266") (pin "1") (pinfunction "1_1") (pintype "passive"))
      (node (ref "C267") (pin "1") (pinfunction "1_1") (pintype "passive"))
      (node (ref "C268") (pin "1") (pinfunction "1_1") (pintype "passive"))
      (node (ref "C269") (pin "1") (pinfunction "1_1") (pintype "passive"))
      (node (ref "C270") (pin "1") (pinfunction "1_1") (pintype "passive"))
      (node (ref "C271") (pin "1") (pinfunction "1_1") (pintype "passive"))
      (node (ref "C272") (pin "1") (pinfunction "1_1") (pintype "passive"))
      (node (ref "C273") (pin "1") (pinfunction "1_1") (pintype "passive"))
      (node (ref "C274") (pin "1") (pinfunction "1_1") (pintype "passive"))
      (node (ref "C275") (pin "1") (pinfunction "1_1") (pintype "passive"))
      (node (ref "C276") (pin "1") (pinfunction "1_1") (pintype "passive"))
      (node (ref "C277") (pin "1") (pinfunction "1_1") (pintype "passive"))
      (node (ref "C280") (pin "1") (pinfunction "1_1") (pintype "passive"))
      (node (ref "C281") (pin "1") (pinfunction "1_1") (pintype "passive"))
      (node (ref "C412") (pin "1") (pinfunction "1_1") (pintype "passive"))
      (node (ref "J19") (pin "LB1") (pinfunction "VEET_LB1") (pintype "power_in"))
      (node (ref "J19") (pin "LB10") (pinfunction "VEER_LB10") (pintype "power_in"))
      (node (ref "J19") (pin "LB11") (pinfunction "VEER_LB11") (pintype "power_in"))
      (node (ref "J19") (pin "LB14") (pinfunction "VEER_LB14") (pintype "power_in"))
      (node (ref "J19") (pin "LB17") (pinfunction "VEET_LB17") (pintype "power_in"))
      (node (ref "J19") (pin "LB20") (pinfunction "VEET_LB20") (pintype "power_in"))
      (node (ref "J19") (pin "LT1") (pinfunction "VEET_LT1") (pintype "power_in"))
      (node (ref "J19") (pin "LT10") (pinfunction "VEER_LT10") (pintype "power_in"))
      (node (ref "J19") (pin "LT11") (pinfunction "VEER_LT11") (pintype "power_in"))
      (node (ref "J19") (pin "LT14") (pinfunction "VEER_LT14") (pintype "power_in"))
      (node (ref "J19") (pin "LT17") (pinfunction "VEET_LT17") (pintype "power_in"))
      (node (ref "J19") (pin "LT20") (pinfunction "VEET_LT20") (pintype "power_in"))
      (node (ref "J19") (pin "RB1") (pinfunction "VEET_RB1") (pintype "power_in"))
      (node (ref "J19") (pin "RB10") (pinfunction "VEER_RB10") (pintype "power_in"))
      (node (ref "J19") (pin "RB11") (pinfunction "VEER_RB11") (pintype "power_in"))
      (node (ref "J19") (pin "RB14") (pinfunction "VEER_RB14") (pintype "power_in"))
      (node (ref "J19") (pin "RB17") (pinfunction "VEET_RB17") (pintype "power_in"))
      (node (ref "J19") (pin "RB20") (pinfunction "VEET_RB20") (pintype "power_in"))
      (node (ref "J19") (pin "RT1") (pinfunction "VEET_RT1") (pintype "power_in"))
      (node (ref "J19") (pin "RT10") (pinfunction "VEER_RT10") (pintype "power_in"))
      (node (ref "J19") (pin "RT11") (pinfunction "VEER_RT11") (pintype "power_in"))
      (node (ref "J19") (pin "RT14") (pinfunction "VEER_RT14") (pintype "power_in"))
      (node (ref "J19") (pin "RT17") (pinfunction "VEET_RT17") (pintype "power_in"))
      (node (ref "J19") (pin "RT20") (pinfunction "VEET_RT20") (pintype "power_in"))
      (node (ref "R130") (pin "1") (pinfunction "1_1") (pintype "passive"))
      (node (ref "R140") (pin "1") (pinfunction "1_1") (pintype "passive"))
      (node (ref "R141") (pin "1") (pinfunction "1_1") (pintype "passive"))
      (node (ref "R193") (pin "1") (pinfunction "1_1") (pintype "passive"))
      (node (ref "R213") (pin "1") (pinfunction "1_1") (pintype "passive"))
      (node (ref "R215") (pin "1") (pinfunction "1_1") (pintype "passive"))
      (node (ref "R222") (pin "1") (pinfunction "1_1") (pintype "passive"))
      (node (ref "R223") (pin "1") (pinfunction "1_1") (pintype "passive"))
      (node (ref "T11") (pin "2") (pinfunction "S_2") (pintype "passive"))
      (node (ref "T16") (pin "2") (pinfunction "S_2") (pintype "passive"))
      (node (ref "T17") (pin "2") (pinfunction "S_2") (pintype "passive"))
      (node (ref "T18") (pin "2") (pinfunction "S_2") (pintype "passive"))
    )
    (net (code "27") (name "Net-(J19A-LOS)") (class "Default")
      (node (ref "J19") (pin "LT8") (pinfunction "LOS_LT8") (pintype "output"))
      (node (ref "R135") (pin "1") (pinfunction "1_1") (pintype "passive"))
    )
    (net (code "28") (name "Net-(J19A-MOD_DEF0)") (class "Default")
      (node (ref "J19") (pin "LT6") (pinfunction "MOD_DEF0_LT6") (pintype "output"))
      (node (ref "R136") (pin "1") (pinfunction "1_1") (pintype "passive"))
    )
    (net (code "29") (name "Net-(J19A-RATE_SELECT)") (class "Default")
      (node (ref "J19") (pin "LT7") (pinfunction "RATE_SELECT_LT7") (pintype "input"))
      (node (ref "R140") (pin "2") (pinfunction "2_2") (pintype "passive"))
    )
    (net (code "30") (name "Net-(J19A-TX_FAULT)") (class "Default")
      (node (ref "J19") (pin "LT2") (pinfunction "TX_FAULT_LT2") (pintype "output"))
      (node (ref "R133") (pin "1") (pinfunction "1_1") (pintype "passive"))
    )
    (net (code "31") (name "Net-(J19A-VCCR)") (class "Default")
      (node (ref "C260") (pin "2") (pinfunction "2_2") (pintype "passive"))
      (node (ref "C261") (pin "2") (pinfunction "2_2") (pintype "passive"))
      (node (ref "C262") (pin "2") (pinfunction "2_2") (pintype "passive"))
      (node (ref "C263") (pin "2") (pinfunction "2_2") (pintype "passive"))
      (node (ref "J19") (pin "LT15") (pinfunction "VCCR_LT15") (pintype "power_in"))
      (node (ref "L30") (pin "2") (pinfunction "2_2") (pintype "passive"))
    )
    (net (code "32") (name "Net-(J19A-VCCT)") (class "Default")
      (node (ref "C264") (pin "2") (pinfunction "2_2") (pintype "passive"))
      (node (ref "C265") (pin "2") (pinfunction "2_2") (pintype "passive"))
      (node (ref "J19") (pin "LT16") (pinfunction "VCCT_LT16") (pintype "power_in"))
      (node (ref "L31") (pin "2") (pinfunction "2_2") (pintype "passive"))
    )
    (net (code "33") (name "Net-(J19A-VEER-PadLT9)") (class "Default")
      (node (ref "J19") (pin "LT9") (pinfunction "VEER_LT9") (pintype "power_in"))
      (node (ref "R141") (pin "2") (pinfunction "2_2") (pintype "passive"))
    )
    (net (code "34") (name "Net-(J19B-LOS)") (class "Default")
      (node (ref "J19") (pin "LB8") (pinfunction "LOS_LB8") (pintype "output"))
      (node (ref "R138") (pin "1") (pinfunction "1_1") (pintype "passive"))
    )
    (net (code "35") (name "Net-(J19B-MOD_DEF0)") (class "Default")
      (node (ref "J19") (pin "LB6") (pinfunction "MOD_DEF0_LB6") (pintype "output"))
      (node (ref "R137") (pin "1") (pinfunction "1_1") (pintype "passive"))
    )
    (net (code "36") (name "Net-(J19B-RATE_SELECT)") (class "Default")
      (node (ref "J19") (pin "LB7") (pinfunction "RATE_SELECT_LB7") (pintype "input"))
      (node (ref "R213") (pin "2") (pinfunction "2_2") (pintype "passive"))
    )
    (net (code "37") (name "Net-(J19B-TX_FAULT)") (class "Default")
      (node (ref "J19") (pin "LB2") (pinfunction "TX_FAULT_LB2") (pintype "output"))
      (node (ref "R134") (pin "1") (pinfunction "1_1") (pintype "passive"))
    )
    (net (code "38") (name "Net-(J19B-VCCR)") (class "Default")
      (node (ref "C179") (pin "2") (pinfunction "2_2") (pintype "passive"))
      (node (ref "C180") (pin "2") (pinfunction "2_2") (pintype "passive"))
      (node (ref "C181") (pin "2") (pinfunction "2_2") (pintype "passive"))
      (node (ref "C182") (pin "2") (pinfunction "2_2") (pintype "passive"))
      (node (ref "J19") (pin "LB15") (pinfunction "VCCR_LB15") (pintype "power_in"))
      (node (ref "L20") (pin "2") (pinfunction "2_2") (pintype "passive"))
    )
    (net (code "39") (name "Net-(J19B-VCCT)") (class "Default")
      (node (ref "C183") (pin "2") (pinfunction "2_2") (pintype "passive"))
      (node (ref "C184") (pin "2") (pinfunction "2_2") (pintype "passive"))
      (node (ref "J19") (pin "LB16") (pinfunction "VCCT_LB16") (pintype "power_in"))
      (node (ref "L21") (pin "2") (pinfunction "2_2") (pintype "passive"))
    )
    (net (code "40") (name "Net-(J19B-VEER-PadLB9)") (class "Default")
      (node (ref "J19") (pin "LB9") (pinfunction "VEER_LB9") (pintype "power_in"))
      (node (ref "R130") (pin "2") (pinfunction "2_2") (pintype "passive"))
    )
    (net (code "41") (name "Net-(J19C-LOS)") (class "Default")
      (node (ref "J19") (pin "RT8") (pinfunction "LOS_RT8") (pintype "output"))
      (node (ref "R218") (pin "1") (pinfunction "1_1") (pintype "passive"))
    )
    (net (code "42") (name "Net-(J19C-MOD_DEF0)") (class "Default")
      (node (ref "J19") (pin "RT6") (pinfunction "MOD_DEF0_RT6") (pintype "output"))
      (node (ref "R219") (pin "1") (pinfunction "1_1") (pintype "passive"))
    )
    (net (code "43") (name "Net-(J19C-RATE_SELECT)") (class "Default")
      (node (ref "J19") (pin "RT7") (pinfunction "RATE_SELECT_RT7") (pintype "input"))
      (node (ref "R222") (pin "2") (pinfunction "2_2") (pintype "passive"))
    )
    (net (code "44") (name "Net-(J19C-TX_FAULT)") (class "Default")
      (node (ref "J19") (pin "RT2") (pinfunction "TX_FAULT_RT2") (pintype "output"))
      (node (ref "R217") (pin "1") (pinfunction "1_1") (pintype "passive"))
    )
    (net (code "45") (name "Net-(J19C-VCCR)") (class "Default")
      (node (ref "C274") (pin "2") (pinfunction "2_2") (pintype "passive"))
      (node (ref "C275") (pin "2") (pinfunction "2_2") (pintype "passive"))
      (node (ref "C277") (pin "2") (pinfunction "2_2") (pintype "passive"))
      (node (ref "C281") (pin "2") (pinfunction "2_2") (pintype "passive"))
      (node (ref "J19") (pin "RT15") (pinfunction "VCCR_RT15") (pintype "power_in"))
      (node (ref "L19") (pin "2") (pinfunction "2_2") (pintype "passive"))
    )
    (net (code "46") (name "Net-(J19C-VCCT)") (class "Default")
      (node (ref "C280") (pin "2") (pinfunction "2_2") (pintype "passive"))
      (node (ref "C412") (pin "2") (pinfunction "2_2") (pintype "passive"))
      (node (ref "J19") (pin "RT16") (pinfunction "VCCT_RT16") (pintype "power_in"))
      (node (ref "L34") (pin "2") (pinfunction "2_2") (pintype "passive"))
    )
    (net (code "47") (name "Net-(J19C-VEER-PadRT9)") (class "Default")
      (node (ref "J19") (pin "RT9") (pinfunction "VEER_RT9") (pintype "power_in"))
      (node (ref "R223") (pin "2") (pinfunction "2_2") (pintype "passive"))
    )
    (net (code "48") (name "Net-(J19D-LOS)") (class "Default")
      (node (ref "J19") (pin "RB8") (pinfunction "LOS_RB8") (pintype "output"))
      (node (ref "R145") (pin "1") (pinfunction "1_1") (pintype "passive"))
    )
    (net (code "49") (name "Net-(J19D-MOD_DEF0)") (class "Default")
      (node (ref "J19") (pin "RB6") (pinfunction "MOD_DEF0_RB6") (pintype "output"))
      (node (ref "R174") (pin "1") (pinfunction "1_1") (pintype "passive"))
    )
    (net (code "50") (name "Net-(J19D-RATE_SELECT)") (class "Default")
      (node (ref "J19") (pin "RB7") (pinfunction "RATE_SELECT_RB7") (pintype "input"))
      (node (ref "R193") (pin "2") (pinfunction "2_2") (pintype "passive"))
    )
    (net (code "51") (name "Net-(J19D-TX_FAULT)") (class "Default")
      (node (ref "J19") (pin "RB2") (pinfunction "TX_FAULT_RB2") (pintype "output"))
      (node (ref "R144") (pin "1") (pinfunction "1_1") (pintype "passive"))
    )
    (net (code "52") (name "Net-(J19D-VCCR)") (class "Default")
      (node (ref "C268") (pin "2") (pinfunction "2_2") (pintype "passive"))
      (node (ref "C269") (pin "2") (pinfunction "2_2") (pintype "passive"))
      (node (ref "C270") (pin "2") (pinfunction "2_2") (pintype "passive"))
      (node (ref "C271") (pin "2") (pinfunction "2_2") (pintype "passive"))
      (node (ref "J19") (pin "RB15") (pinfunction "VCCR_RB15") (pintype "power_in"))
      (node (ref "L32") (pin "2") (pinfunction "2_2") (pintype "passive"))
    )
    (net (code "53") (name "Net-(J19D-VCCT)") (class "Default")
      (node (ref "C272") (pin "2") (pinfunction "2_2") (pintype "passive"))
      (node (ref "C273") (pin "2") (pinfunction "2_2") (pintype "passive"))
      (node (ref "J19") (pin "RB16") (pinfunction "VCCT_RB16") (pintype "power_in"))
      (node (ref "L33") (pin "2") (pinfunction "2_2") (pintype "passive"))
    )
    (net (code "54") (name "Net-(J19D-VEER-PadRB9)") (class "Default")
      (node (ref "J19") (pin "RB9") (pinfunction "VEER_RB9") (pintype "power_in"))
      (node (ref "R215") (pin "2") (pinfunction "2_2") (pintype "passive"))
    )
    (net (code "55") (name "Net-(LD11-C)") (class "Default")
      (node (ref "LD11") (pin "1") (pinfunction "C_1") (pintype "passive"))
      (node (ref "R143") (pin "2") (pinfunction "2_2") (pintype "passive"))
    )
    (net (code "56") (name "Net-(LD15-C)") (class "Default")
      (node (ref "LD15") (pin "1") (pinfunction "C_1") (pintype "passive"))
      (node (ref "R142") (pin "2") (pinfunction "2_2") (pintype "passive"))
    )
    (net (code "57") (name "Net-(LD16-C)") (class "Default")
      (node (ref "LD16") (pin "1") (pinfunction "C_1") (pintype "passive"))
      (node (ref "R216") (pin "2") (pinfunction "2_2") (pintype "passive"))
    )
    (net (code "58") (name "Net-(LD17-C)") (class "Default")
      (node (ref "LD17") (pin "1") (pinfunction "C_1") (pintype "passive"))
      (node (ref "R220") (pin "2") (pinfunction "2_2") (pintype "passive"))
    )
    (net (code "59") (name "Net-(T11-D)") (class "Default")
      (node (ref "R143") (pin "1") (pinfunction "1_1") (pintype "passive"))
      (node (ref "T11") (pin "3") (pinfunction "D_3") (pintype "passive"))
    )
    (net (code "60") (name "Net-(T16-D)") (class "Default")
      (node (ref "R142") (pin "1") (pinfunction "1_1") (pintype "passive"))
      (node (ref "T16") (pin "3") (pinfunction "D_3") (pintype "passive"))
    )
    (net (code "61") (name "Net-(T17-D)") (class "Default")
      (node (ref "R216") (pin "1") (pinfunction "1_1") (pintype "passive"))
      (node (ref "T17") (pin "3") (pinfunction "D_3") (pintype "passive"))
    )
    (net (code "62") (name "Net-(T18-D)") (class "Default")
      (node (ref "R220") (pin "1") (pinfunction "1_1") (pintype "passive"))
      (node (ref "T18") (pin "3") (pinfunction "D_3") (pintype "passive"))
    )
    (net (code "63") (name "P3V3") (class "Default")
      (node (ref "C160") (pin "2") (pinfunction "2_2") (pintype "passive"))
      (node (ref "C178") (pin "2") (pinfunction "2_2") (pintype "passive"))
      (node (ref "C185") (pin "2") (pinfunction "2_2") (pintype "passive"))
      (node (ref "C244") (pin "2") (pinfunction "2_2") (pintype "passive"))
      (node (ref "C259") (pin "2") (pinfunction "2_2") (pintype "passive"))
      (node (ref "C266") (pin "2") (pinfunction "2_2") (pintype "passive"))
      (node (ref "C267") (pin "2") (pinfunction "2_2") (pintype "passive"))
      (node (ref "C276") (pin "2") (pinfunction "2_2") (pintype "passive"))
      (node (ref "L19") (pin "1") (pinfunction "1_1") (pintype "passive"))
      (node (ref "L20") (pin "1") (pinfunction "1_1") (pintype "passive"))
      (node (ref "L21") (pin "1") (pinfunction "1_1") (pintype "passive"))
      (node (ref "L30") (pin "1") (pinfunction "1_1") (pintype "passive"))
      (node (ref "L31") (pin "1") (pinfunction "1_1") (pintype "passive"))
      (node (ref "L32") (pin "1") (pinfunction "1_1") (pintype "passive"))
      (node (ref "L33") (pin "1") (pinfunction "1_1") (pintype "passive"))
      (node (ref "L34") (pin "1") (pinfunction "1_1") (pintype "passive"))
      (node (ref "LD11") (pin "2") (pinfunction "A_2") (pintype "passive"))
      (node (ref "LD15") (pin "2") (pinfunction "A_2") (pintype "passive"))
      (node (ref "LD16") (pin "2") (pinfunction "A_2") (pintype "passive"))
      (node (ref "LD17") (pin "2") (pinfunction "A_2") (pintype "passive"))
      (node (ref "R133") (pin "2") (pinfunction "2_2") (pintype "passive"))
      (node (ref "R134") (pin "2") (pinfunction "2_2") (pintype "passive"))
      (node (ref "R135") (pin "2") (pinfunction "2_2") (pintype "passive"))
      (node (ref "R136") (pin "2") (pinfunction "2_2") (pintype "passive"))
      (node (ref "R137") (pin "2") (pinfunction "2_2") (pintype "passive"))
      (node (ref "R138") (pin "2") (pinfunction "2_2") (pintype "passive"))
      (node (ref "R144") (pin "2") (pinfunction "2_2") (pintype "passive"))
      (node (ref "R145") (pin "2") (pinfunction "2_2") (pintype "passive"))
      (node (ref "R174") (pin "2") (pinfunction "2_2") (pintype "passive"))
      (node (ref "R217") (pin "2") (pinfunction "2_2") (pintype "passive"))
      (node (ref "R218") (pin "2") (pinfunction "2_2") (pintype "passive"))
      (node (ref "R219") (pin "2") (pinfunction "2_2") (pintype "passive"))
    )
    (net (code "64") (name "unconnected-(C246-Pad2)") (class "Default")
      (node (ref "C246") (pin "2") (pinfunction "2_2") (pintype "passive"))
    )
    (net (code "65") (name "unconnected-(C247-Pad2)") (class "Default")
      (node (ref "C247") (pin "2") (pinfunction "2_2") (pintype "passive"))
    )
    (net (code "66") (name "unconnected-(C248-Pad2)") (class "Default")
      (node (ref "C248") (pin "2") (pinfunction "2_2") (pintype "passive"))
    )
    (net (code "67") (name "unconnected-(C249-Pad2)") (class "Default")
      (node (ref "C249") (pin "2") (pinfunction "2_2") (pintype "passive"))
    )
    (net (code "68") (name "unconnected-(C250-Pad2)") (class "Default")
      (node (ref "C250") (pin "2") (pinfunction "2_2") (pintype "passive"))
    )
    (net (code "69") (name "unconnected-(C251-Pad2)") (class "Default")
      (node (ref "C251") (pin "2") (pinfunction "2_2") (pintype "passive"))
    )
    (net (code "70") (name "unconnected-(C252-Pad2)") (class "Default")
      (node (ref "C252") (pin "2") (pinfunction "2_2") (pintype "passive"))
    )
    (net (code "71") (name "unconnected-(C253-Pad2)") (class "Default")
      (node (ref "C253") (pin "2") (pinfunction "2_2") (pintype "passive"))
    )
    (net (code "72") (name "unconnected-(C254-Pad2)") (class "Default")
      (node (ref "C254") (pin "2") (pinfunction "2_2") (pintype "passive"))
    )
    (net (code "73") (name "unconnected-(C255-Pad2)") (class "Default")
      (node (ref "C255") (pin "2") (pinfunction "2_2") (pintype "passive"))
    )
    (net (code "74") (name "unconnected-(C256-Pad2)") (class "Default")
      (node (ref "C256") (pin "2") (pinfunction "2_2") (pintype "passive"))
    )
    (net (code "75") (name "unconnected-(C257-Pad2)") (class "Default")
      (node (ref "C257") (pin "2") (pinfunction "2_2") (pintype "passive"))
    )
    (net (code "76") (name "unconnected-(C282-Pad2)") (class "Default")
      (node (ref "C282") (pin "2") (pinfunction "2_2") (pintype "passive"))
    )
    (net (code "77") (name "unconnected-(C283-Pad2)") (class "Default")
      (node (ref "C283") (pin "2") (pinfunction "2_2") (pintype "passive"))
    )
    (net (code "78") (name "unconnected-(C284-Pad2)") (class "Default")
      (node (ref "C284") (pin "2") (pinfunction "2_2") (pintype "passive"))
    )
    (net (code "79") (name "unconnected-(C285-Pad2)") (class "Default")
      (node (ref "C285") (pin "2") (pinfunction "2_2") (pintype "passive"))
    )
    (net (code "80") (name "unconnected-(J19A-MOD_DEF1-PadLT5)") (class "Default")
      (node (ref "J19") (pin "LT5") (pinfunction "MOD_DEF1_LT5") (pintype "input"))
    )
    (net (code "81") (name "unconnected-(J19A-MOD_DEF2-PadLT4)") (class "Default")
      (node (ref "J19") (pin "LT4") (pinfunction "MOD_DEF2_LT4") (pintype "bidirectional"))
    )
    (net (code "82") (name "unconnected-(J19A-TX_DISABLE-PadLT3)") (class "Default")
      (node (ref "J19") (pin "LT3") (pinfunction "TX_DISABLE_LT3") (pintype "input"))
    )
    (net (code "83") (name "unconnected-(J19B-MOD_DEF1-PadLB5)") (class "Default")
      (node (ref "J19") (pin "LB5") (pinfunction "MOD_DEF1_LB5") (pintype "input"))
    )
    (net (code "84") (name "unconnected-(J19B-MOD_DEF2-PadLB4)") (class "Default")
      (node (ref "J19") (pin "LB4") (pinfunction "MOD_DEF2_LB4") (pintype "bidirectional"))
    )
    (net (code "85") (name "unconnected-(J19B-TX_DISABLE-PadLB3)") (class "Default")
      (node (ref "J19") (pin "LB3") (pinfunction "TX_DISABLE_LB3") (pintype "input"))
    )
    (net (code "86") (name "unconnected-(J19C-MOD_DEF1-PadRT5)") (class "Default")
      (node (ref "J19") (pin "RT5") (pinfunction "MOD_DEF1_RT5") (pintype "input"))
    )
    (net (code "87") (name "unconnected-(J19C-MOD_DEF2-PadRT4)") (class "Default")
      (node (ref "J19") (pin "RT4") (pinfunction "MOD_DEF2_RT4") (pintype "bidirectional"))
    )
    (net (code "88") (name "unconnected-(J19C-TX_DISABLE-PadRT3)") (class "Default")
      (node (ref "J19") (pin "RT3") (pinfunction "TX_DISABLE_RT3") (pintype "input"))
    )
    (net (code "89") (name "unconnected-(J19D-MOD_DEF1-PadRB5)") (class "Default")
      (node (ref "J19") (pin "RB5") (pinfunction "MOD_DEF1_RB5") (pintype "input"))
    )
    (net (code "90") (name "unconnected-(J19D-MOD_DEF2-PadRB4)") (class "Default")
      (node (ref "J19") (pin "RB4") (pinfunction "MOD_DEF2_RB4") (pintype "bidirectional"))
    )
    (net (code "91") (name "unconnected-(J19D-TX_DISABLE-PadRB3)") (class "Default")
      (node (ref "J19") (pin "RB3") (pinfunction "TX_DISABLE_RB3") (pintype "input"))
    )
  )
)
